# board.net
KiCad netlist of a schematic drawn in EAGLE
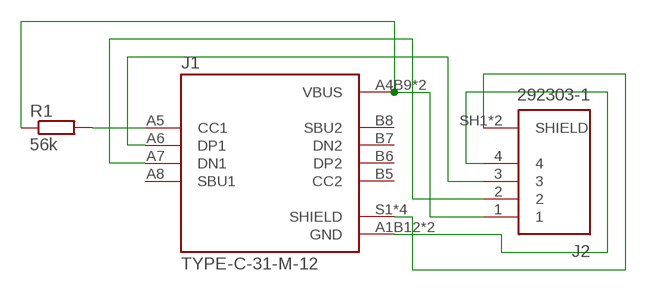
[diagram p0: schematic, sheet 1]

(export (version "E")
  (design (tool "Eeschema 10.0.6"))
  (components
    (comp (ref "J1")
      (value "TYPE-C-31-M-12")
      (footprint "eagle-import:HRO_TYPE-C-31-M-12")
      (fields (field (name "MF") "HRO Electronics Co., Ltd."))
      (libsource (lib "eagle-import") (part "TYPE-C-31-M-12"))
    )
    (comp (ref "J2")
      (value "292303-1")
      (footprint "eagle-import:292303-1")
      (fields
        (field (name "DIGIKEY_PARTNO") "A31726-ND")
        (field (name "MANUFACTURER") "TE Connectivity AMP Connectors")
        (field (name "CREATED_BY") "PCBLayout.com")
      )
      (libsource (lib "eagle-import") (part "292303-1"))
    )
    (comp (ref "R1")
      (value "56k")
      (footprint "eagle-import:R0603")
      (libsource (lib "eagle-import") (part "RESISTOR-0603"))
    )
  )
  (nets
    (net (code "1") (name "Net-(J1-CC1)") (class "Default")
      (node (ref "J1") (pin "A5") (pinfunction "CC1_A5") (pintype "bidirectional"))
      (node (ref "R1") (pin "2") (pinfunction "2_2") (pintype "passive"))
    )
    (net (code "2") (name "Net-(J1-DN1)") (class "Default")
      (node (ref "J1") (pin "A7") (pinfunction "DN1_A7") (pintype "bidirectional"))
      (node (ref "J2") (pin "2") (pinfunction "2_2") (pintype "passive"))
    )
    (net (code "3") (name "Net-(J1-DP1)") (class "Default")
      (node (ref "J1") (pin "A6") (pinfunction "DP1_A6") (pintype "bidirectional"))
      (node (ref "J2") (pin "3") (pinfunction "3_3") (pintype "passive"))
    )
    (net (code "4") (name "Net-(J1-GND-PadA1B12)") (class "Default")
      (node (ref "J1") (pin "A1B12") (pinfunction "GND_A1B12") (pintype "power_in"))
      (node (ref "J1") (pin "B1A12") (pinfunction "GND_B1A12") (pintype "power_in"))
      (node (ref "J2") (pin "4") (pinfunction "4_4") (pintype "passive"))
    )
    (net (code "5") (name "Net-(J1-SHIELD-PadS1)") (class "Default")
      (node (ref "J1") (pin "S1") (pinfunction "SHIELD_S1") (pintype "passive"))
      (node (ref "J1") (pin "S2") (pinfunction "SHIELD_S2") (pintype "passive"))
      (node (ref "J1") (pin "S3") (pinfunction "SHIELD_S3") (pintype "passive"))
      (node (ref "J1") (pin "S4") (pinfunction "SHIELD_S4") (pintype "passive"))
      (node (ref "J2") (pin "SH1") (pinfunction "SHIELD_SH1") (pintype "power_in"))
      (node (ref "J2") (pin "SH2") (pinfunction "SHIELD_SH2") (pintype "power_in"))
    )
    (net (code "6") (name "Net-(J1-VBUS-PadA4B9)") (class "Default")
      (node (ref "J1") (pin "A4B9") (pinfunction "VBUS_A4B9") (pintype "power_in"))
      (node (ref "J1") (pin "B4A9") (pinfunction "VBUS_B4A9") (pintype "power_in"))
      (node (ref "J2") (pin "1") (pinfunction "1_1") (pintype "passive"))
      (node (ref "R1") (pin "1") (pinfunction "1_1") (pintype "passive"))
    )
    (net (code "7") (name "unconnected-(J1-CC2-PadB5)") (class "Default")
      (node (ref "J1") (pin "B5") (pinfunction "CC2_B5") (pintype "bidirectional"))
    )
    (net (code "8") (name "unconnected-(J1-DN2-PadB7)") (class "Default")
      (node (ref "J1") (pin "B7") (pinfunction "DN2_B7") (pintype "bidirectional"))
    )
    (net (code "9") (name "unconnected-(J1-DP2-PadB6)") (class "Default")
      (node (ref "J1") (pin "B6") (pinfunction "DP2_B6") (pintype "bidirectional"))
    )
    (net (code "10") (name "unconnected-(J1-SBU1-PadA8)") (class "Default")
      (node (ref "J1") (pin "A8") (pinfunction "SBU1_A8") (pintype "bidirectional"))
    )
    (net (code "11") (name "unconnected-(J1-SBU2-PadB8)") (class "Default")
      (node (ref "J1") (pin "B8") (pinfunction "SBU2_B8") (pintype "bidirectional"))
    )
  )
)
